# heater_v1.net
KiCad netlist of a schematic drawn in EAGLE
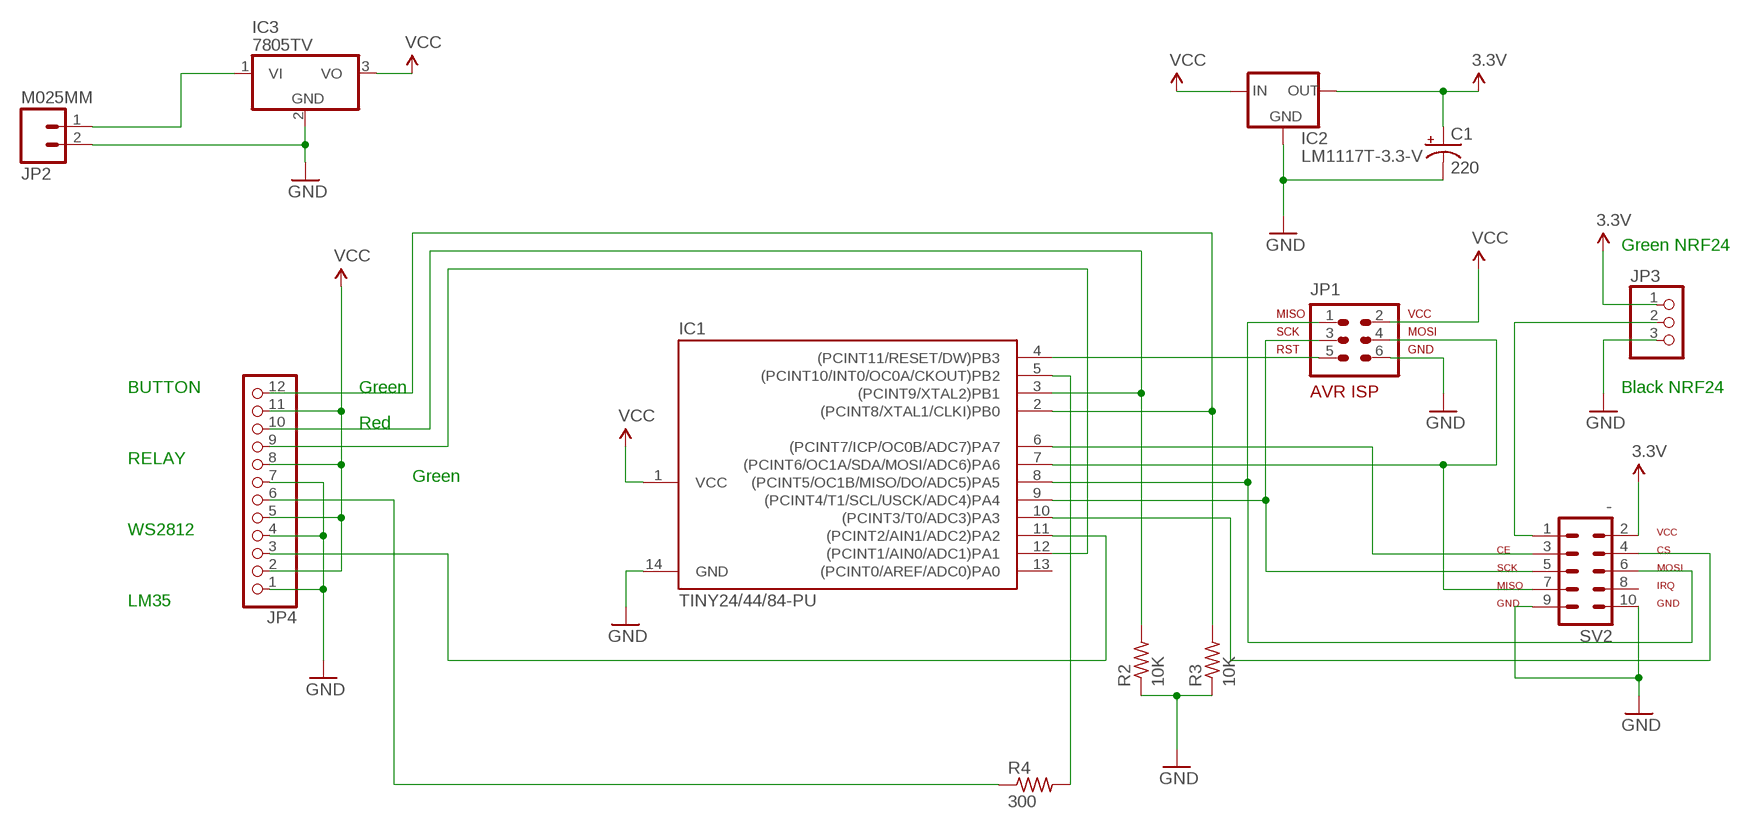
[diagram p0: schematic, sheet 1]

(export (version "E")
  (design (tool "Eeschema 10.0.6"))
  (components
    (comp (ref "C1")
      (value "220")
      (footprint "eagle-import:E2,5-6")
      (libsource (lib "eagle-import") (part "CPOL-USE2.5-6"))
    )
    (comp (ref "IC1")
      (value "TINY24/44/84-PU")
      (footprint "eagle-import:DIL14")
      (libsource (lib "eagle-import") (part "TINY24/44/84-PU"))
    )
    (comp (ref "IC2")
      (value "LM1117T-3.3-V")
      (footprint "eagle-import:TO220V")
      (libsource (lib "eagle-import") (part "LM1117T--V3.3"))
    )
    (comp (ref "IC3")
      (value "7805TV")
      (footprint "eagle-import:TO220V")
      (libsource (lib "eagle-import") (part "78TV05"))
    )
    (comp (ref "JP1")
      (value "AVR-ISP-6VERT")
      (footprint "eagle-import:AVR-ISP-6")
      (libsource (lib "eagle-import") (part "AVR-ISP-6VERT"))
    )
    (comp (ref "JP2")
      (value "M025MM")
      (footprint "eagle-import:SCREWTERMINAL-5MM-2")
      (libsource (lib "eagle-import") (part "M025MM"))
    )
    (comp (ref "JP3")
      (value "PINHD-1X3")
      (footprint "eagle-import:1X03")
      (libsource (lib "eagle-import") (part "PINHD-1X3"))
    )
    (comp (ref "JP4")
      (value "PINHD-1X12-CB")
      (footprint "eagle-import:1X12-CB")
      (libsource (lib "eagle-import") (part "PINHD-1X12-CB"))
    )
    (comp (ref "R2")
      (value "10K")
      (footprint "eagle-import:0204_7")
      (libsource (lib "eagle-import") (part "R-US_0204/7"))
    )
    (comp (ref "R3")
      (value "10K")
      (footprint "eagle-import:0204_7")
      (libsource (lib "eagle-import") (part "R-US_0204/7"))
    )
    (comp (ref "R4")
      (value "300")
      (footprint "eagle-import:0204_7")
      (libsource (lib "eagle-import") (part "R-US_0204/7"))
    )
    (comp (ref "SV2")
      (value "-")
      (footprint "eagle-import:MA05-2")
      (libsource (lib "eagle-import") (part "MA05-2"))
    )
  )
  (nets
    (net (code "1") (name "3.3V") (class "Default")
      (node (ref "C1") (pin "+") (pinfunction "+_+") (pintype "passive"))
      (node (ref "IC2") (pin "2") (pinfunction "OUT_2") (pintype "passive"))
      (node (ref "JP3") (pin "1") (pinfunction "1_1") (pintype "passive"))
      (node (ref "SV2") (pin "2") (pinfunction "2_2") (pintype "passive"))
    )
    (net (code "2") (name "GND") (class "Default")
      (node (ref "C1") (pin "-") (pinfunction "-_-") (pintype "passive"))
      (node (ref "IC1") (pin "14") (pinfunction "GND_14") (pintype "power_in"))
      (node (ref "IC2") (pin "1") (pinfunction "GND_1") (pintype "input"))
      (node (ref "IC3") (pin "2") (pinfunction "GND_2") (pintype "passive"))
      (node (ref "JP1") (pin "6") (pinfunction "6_6") (pintype "passive"))
      (node (ref "JP2") (pin "2") (pinfunction "2_2") (pintype "passive"))
      (node (ref "JP3") (pin "3") (pinfunction "3_3") (pintype "passive"))
      (node (ref "JP4") (pin "1") (pinfunction "1_1") (pintype "passive"))
      (node (ref "JP4") (pin "4") (pinfunction "4_4") (pintype "passive"))
      (node (ref "JP4") (pin "7") (pinfunction "7_7") (pintype "passive"))
      (node (ref "R2") (pin "1") (pinfunction "1_1") (pintype "passive"))
      (node (ref "R3") (pin "1") (pinfunction "1_1") (pintype "passive"))
      (node (ref "SV2") (pin "10") (pinfunction "10_10") (pintype "passive"))
      (node (ref "SV2") (pin "9") (pinfunction "9_9") (pintype "passive"))
    )
    (net (code "3") (name "Net-(IC1-(PCINT1{slash}AIN0{slash}ADC1)PA1)") (class "Default")
      (node (ref "IC1") (pin "12") (pinfunction "(PCINT1/AIN0/ADC1)PA1_12") (pintype "bidirectional"))
      (node (ref "JP4") (pin "9") (pinfunction "9_9") (pintype "passive"))
    )
    (net (code "4") (name "Net-(IC1-(PCINT2{slash}AIN1{slash}ADC2)PA2)") (class "Default")
      (node (ref "IC1") (pin "11") (pinfunction "(PCINT2/AIN1/ADC2)PA2_11") (pintype "bidirectional"))
      (node (ref "JP4") (pin "3") (pinfunction "3_3") (pintype "passive"))
    )
    (net (code "5") (name "Net-(IC1-(PCINT3{slash}T0{slash}ADC3)PA3)") (class "Default")
      (node (ref "IC1") (pin "10") (pinfunction "(PCINT3/T0/ADC3)PA3_10") (pintype "bidirectional"))
      (node (ref "SV2") (pin "4") (pinfunction "4_4") (pintype "passive"))
    )
    (net (code "6") (name "Net-(IC1-(PCINT4{slash}T1{slash}SCL{slash}USCK{slash}ADC4)PA4)") (class "Default")
      (node (ref "IC1") (pin "9") (pinfunction "(PCINT4/T1/SCL/USCK/ADC4)PA4_9") (pintype "bidirectional"))
      (node (ref "JP1") (pin "3") (pinfunction "3_3") (pintype "passive"))
      (node (ref "SV2") (pin "5") (pinfunction "5_5") (pintype "passive"))
    )
    (net (code "7") (name "Net-(IC1-(PCINT5{slash}OC1B{slash}MISO{slash}DO{slash}ADC5)PA5)") (class "Default")
      (node (ref "IC1") (pin "8") (pinfunction "(PCINT5/OC1B/MISO/DO/ADC5)PA5_8") (pintype "bidirectional"))
      (node (ref "JP1") (pin "1") (pinfunction "1_1") (pintype "passive"))
      (node (ref "SV2") (pin "6") (pinfunction "6_6") (pintype "passive"))
    )
    (net (code "8") (name "Net-(IC1-(PCINT6{slash}OC1A{slash}SDA{slash}MOSI{slash}ADC6)PA6)") (class "Default")
      (node (ref "IC1") (pin "7") (pinfunction "(PCINT6/OC1A/SDA/MOSI/ADC6)PA6_7") (pintype "bidirectional"))
      (node (ref "JP1") (pin "4") (pinfunction "4_4") (pintype "passive"))
      (node (ref "SV2") (pin "7") (pinfunction "7_7") (pintype "passive"))
    )
    (net (code "9") (name "Net-(IC1-(PCINT7{slash}ICP{slash}OC0B{slash}ADC7)PA7)") (class "Default")
      (node (ref "IC1") (pin "6") (pinfunction "(PCINT7/ICP/OC0B/ADC7)PA7_6") (pintype "bidirectional"))
      (node (ref "SV2") (pin "3") (pinfunction "3_3") (pintype "passive"))
    )
    (net (code "10") (name "Net-(IC1-(PCINT8{slash}XTAL1{slash}CLKI)PB0)") (class "Default")
      (node (ref "IC1") (pin "2") (pinfunction "(PCINT8/XTAL1/CLKI)PB0_2") (pintype "bidirectional"))
      (node (ref "JP4") (pin "12") (pinfunction "12_12") (pintype "passive"))
      (node (ref "R3") (pin "2") (pinfunction "2_2") (pintype "passive"))
    )
    (net (code "11") (name "Net-(IC1-(PCINT9{slash}XTAL2)PB1)") (class "Default")
      (node (ref "IC1") (pin "3") (pinfunction "(PCINT9/XTAL2)PB1_3") (pintype "bidirectional"))
      (node (ref "JP4") (pin "10") (pinfunction "10_10") (pintype "passive"))
      (node (ref "R2") (pin "2") (pinfunction "2_2") (pintype "passive"))
    )
    (net (code "12") (name "Net-(IC1-(PCINT10{slash}INT0{slash}OC0A{slash}CKOUT)PB2)") (class "Default")
      (node (ref "IC1") (pin "5") (pinfunction "(PCINT10/INT0/OC0A/CKOUT)PB2_5") (pintype "bidirectional"))
      (node (ref "R4") (pin "2") (pinfunction "2_2") (pintype "passive"))
    )
    (net (code "13") (name "Net-(IC1-(PCINT11{slash}RESET{slash}DW)PB3)") (class "Default")
      (node (ref "IC1") (pin "4") (pinfunction "(PCINT11/RESET/DW)PB3_4") (pintype "bidirectional"))
      (node (ref "JP1") (pin "5") (pinfunction "5_5") (pintype "passive"))
    )
    (net (code "14") (name "Net-(IC3-VI)") (class "Default")
      (node (ref "IC3") (pin "1") (pinfunction "VI_1") (pintype "input"))
      (node (ref "JP2") (pin "1") (pinfunction "1_1") (pintype "passive"))
    )
    (net (code "15") (name "Net-(JP3-Pad2)") (class "Default")
      (node (ref "JP3") (pin "2") (pinfunction "2_2") (pintype "passive"))
      (node (ref "SV2") (pin "1") (pinfunction "1_1") (pintype "passive"))
    )
    (net (code "16") (name "Net-(JP4-Pad6)") (class "Default")
      (node (ref "JP4") (pin "6") (pinfunction "6_6") (pintype "passive"))
      (node (ref "R4") (pin "1") (pinfunction "1_1") (pintype "passive"))
    )
    (net (code "17") (name "VCC") (class "Default")
      (node (ref "IC1") (pin "1") (pinfunction "VCC_1") (pintype "power_in"))
      (node (ref "IC2") (pin "3") (pinfunction "IN_3") (pintype "input"))
      (node (ref "IC3") (pin "3") (pinfunction "VO_3") (pintype "passive"))
      (node (ref "JP1") (pin "2") (pinfunction "2_2") (pintype "passive"))
      (node (ref "JP4") (pin "11") (pinfunction "11_11") (pintype "passive"))
      (node (ref "JP4") (pin "2") (pinfunction "2_2") (pintype "passive"))
      (node (ref "JP4") (pin "5") (pinfunction "5_5") (pintype "passive"))
      (node (ref "JP4") (pin "8") (pinfunction "8_8") (pintype "passive"))
    )
    (net (code "18") (name "unconnected-(IC1-(PCINT0{slash}AREF{slash}ADC0)PA0-Pad13)") (class "Default")
      (node (ref "IC1") (pin "13") (pinfunction "(PCINT0/AREF/ADC0)PA0_13") (pintype "bidirectional"))
    )
    (net (code "19") (name "unconnected-(SV2-Pad8)") (class "Default")
      (node (ref "SV2") (pin "8") (pinfunction "8_8") (pintype "passive"))
    )
  )
)
